# 3-7.net
KiCad netlist of a schematic drawn in Altium Designer
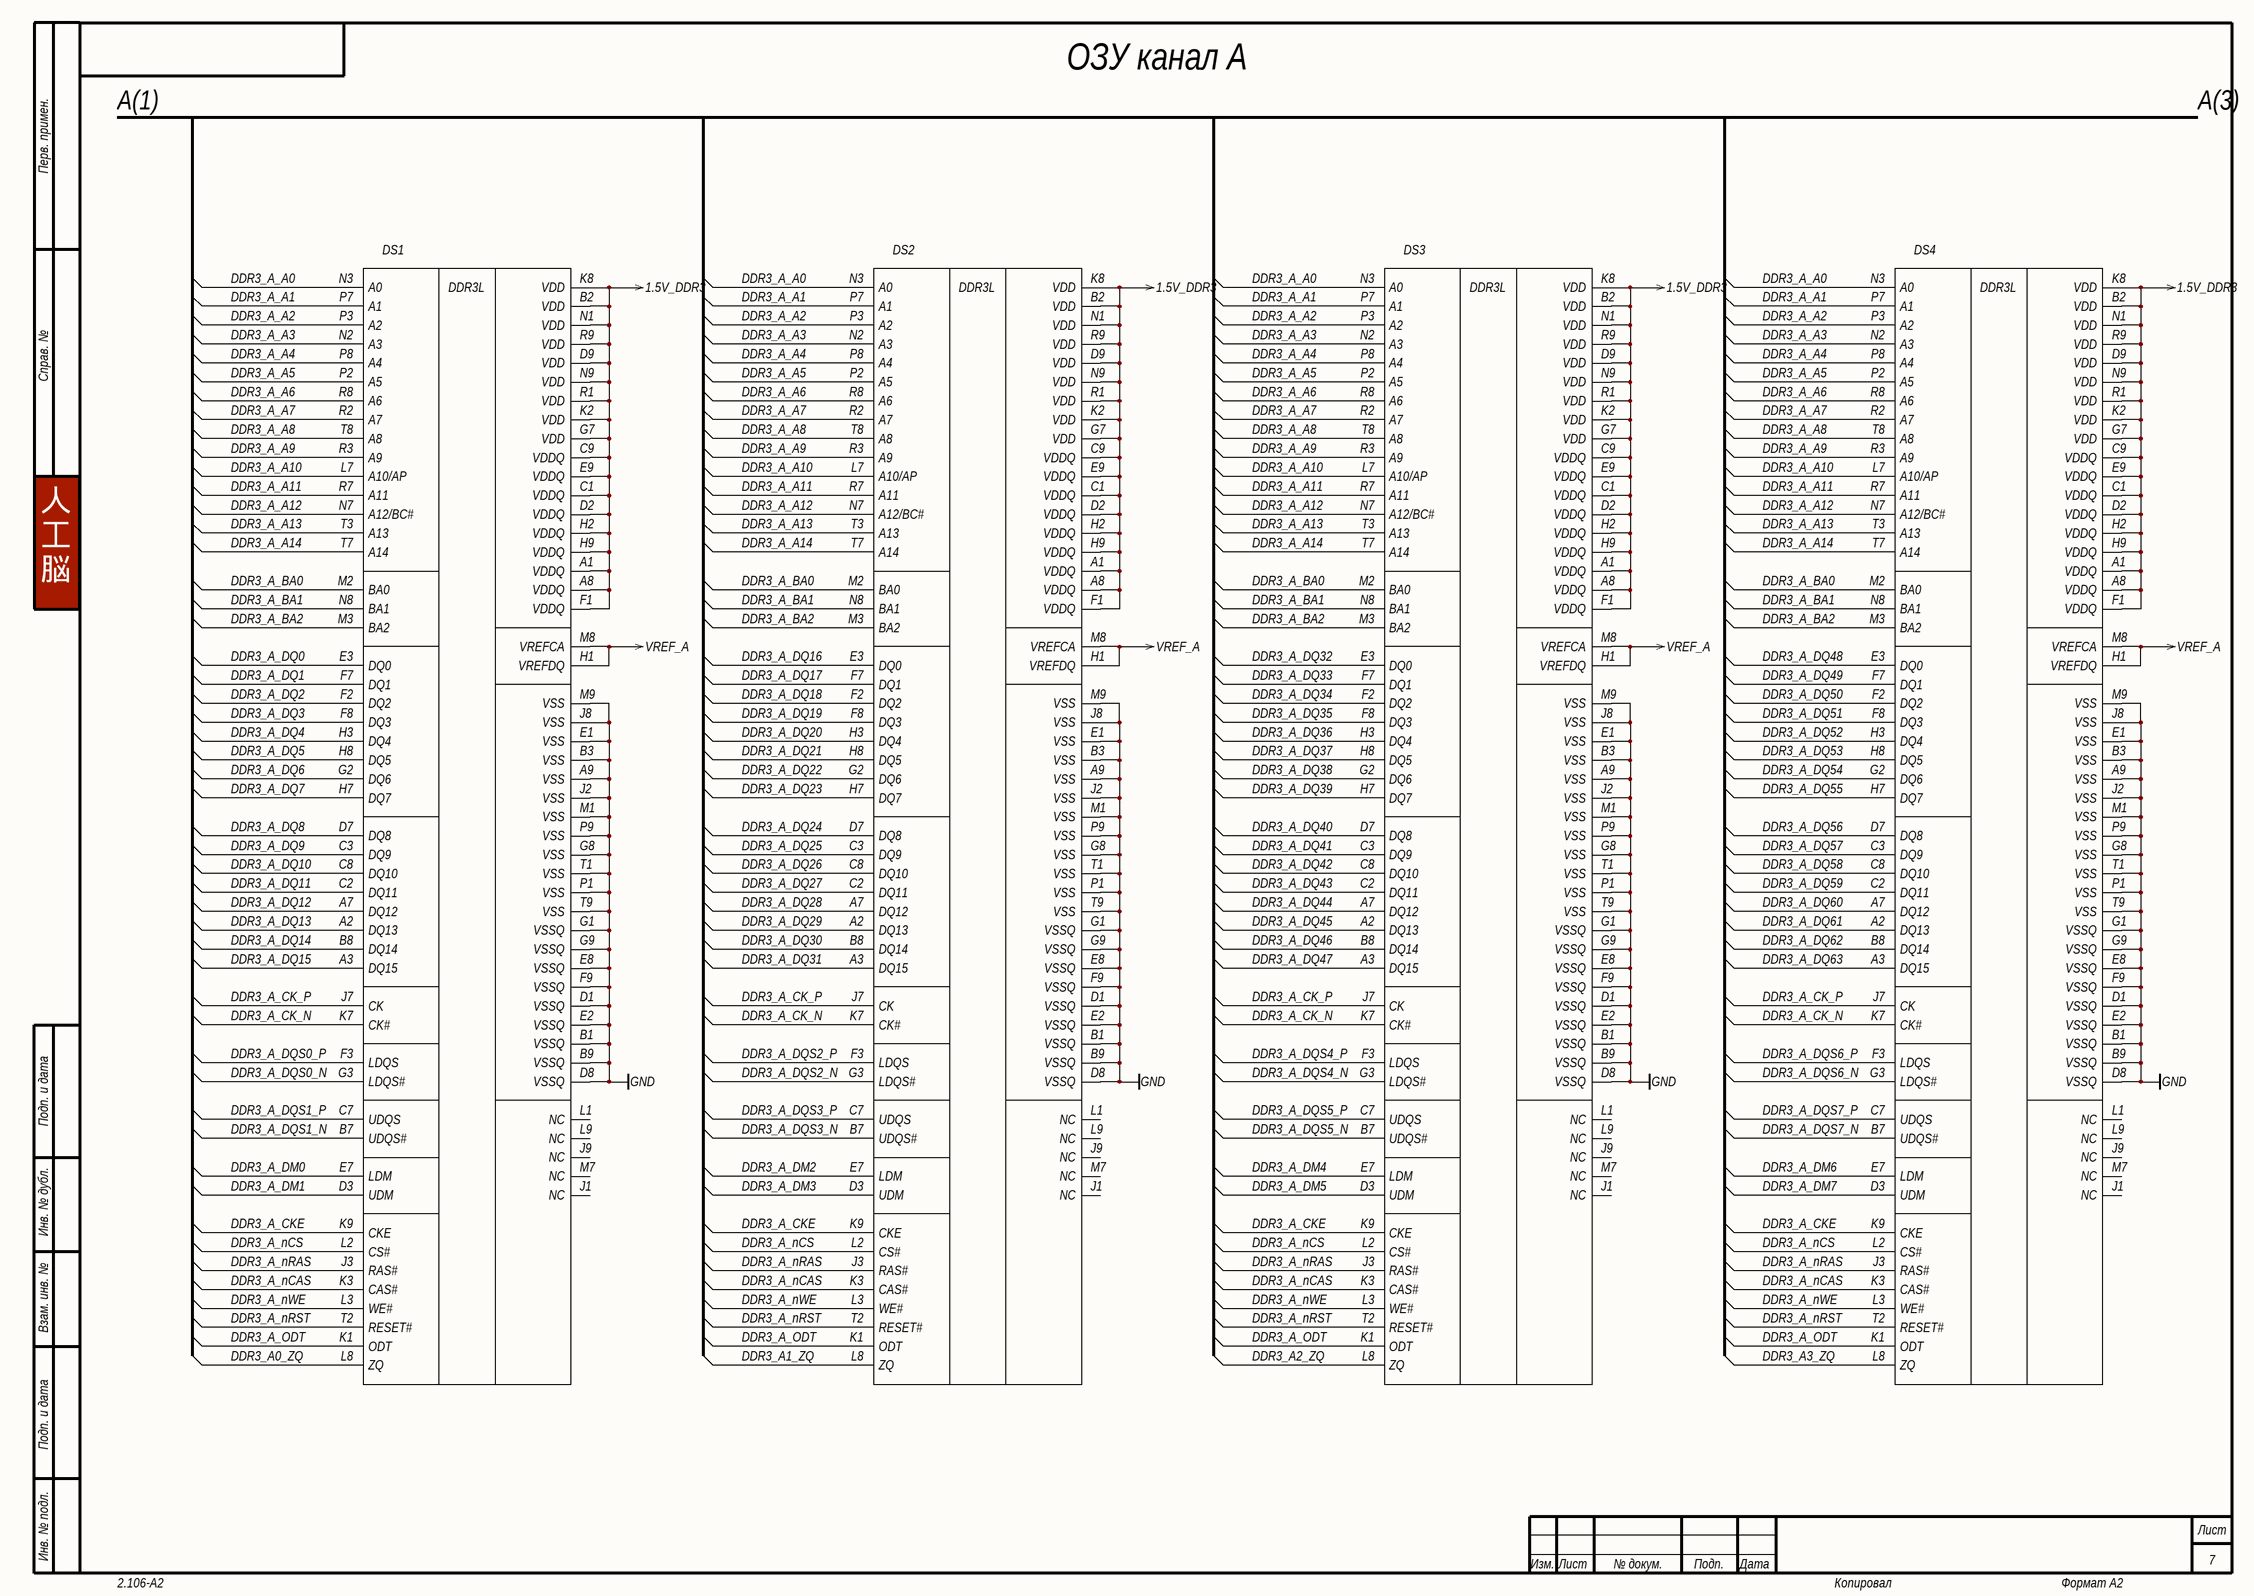
[diagram p0: Э3-7.SchDoc]

(export (version "E")
  (design (tool "Eeschema 10.0.6"))
  (components
    (comp (ref "DS1")
      (value "1")
      (footprint "96-FBGA")
      (description "32 Megx16x8 banks DDR3L SDRAM")
      (fields (field (name "MANUFACTURER") "Micron Technology, Inc."))
      (libsource (lib "Digital") (part "MT41K256M16TW-107IT{colon}P"))
    )
    (comp (ref "DS2")
      (value "1")
      (footprint "96-FBGA")
      (description "32 Megx16x8 banks DDR3L SDRAM")
      (fields (field (name "MANUFACTURER") "Micron Technology, Inc."))
      (libsource (lib "Digital") (part "MT41K256M16TW-107IT{colon}P"))
    )
    (comp (ref "DS3")
      (value "1")
      (footprint "96-FBGA")
      (description "32 Megx16x8 banks DDR3L SDRAM")
      (fields (field (name "MANUFACTURER") "Micron Technology, Inc."))
      (libsource (lib "Digital") (part "MT41K256M16TW-107IT{colon}P"))
    )
    (comp (ref "DS4")
      (value "1")
      (footprint "96-FBGA")
      (description "32 Megx16x8 banks DDR3L SDRAM")
      (fields (field (name "MANUFACTURER") "Micron Technology, Inc."))
      (libsource (lib "Digital") (part "MT41K256M16TW-107IT{colon}P"))
    )
  )
  (nets
    (net (code "1") (name "/DDR3_A0_ZQ") (class "Default")
      (node (ref "DS1") (pin "L8") (pinfunction "ZQ_L8") (pintype "passive"))
    )
    (net (code "2") (name "/DDR3_A1_ZQ") (class "Default")
      (node (ref "DS2") (pin "L8") (pinfunction "ZQ_L8") (pintype "passive"))
    )
    (net (code "3") (name "/DDR3_A2_ZQ") (class "Default")
      (node (ref "DS3") (pin "L8") (pinfunction "ZQ_L8") (pintype "passive"))
    )
    (net (code "4") (name "/DDR3_A3_ZQ") (class "Default")
      (node (ref "DS4") (pin "L8") (pinfunction "ZQ_L8") (pintype "passive"))
    )
    (net (code "5") (name "/DDR3_A_A0") (class "Default")
      (node (ref "DS1") (pin "N3") (pinfunction "A0_N3") (pintype "passive"))
      (node (ref "DS2") (pin "N3") (pinfunction "A0_N3") (pintype "passive"))
      (node (ref "DS3") (pin "N3") (pinfunction "A0_N3") (pintype "passive"))
      (node (ref "DS4") (pin "N3") (pinfunction "A0_N3") (pintype "passive"))
    )
    (net (code "6") (name "/DDR3_A_A1") (class "Default")
      (node (ref "DS1") (pin "P7") (pinfunction "A1_P7") (pintype "passive"))
      (node (ref "DS2") (pin "P7") (pinfunction "A1_P7") (pintype "passive"))
      (node (ref "DS3") (pin "P7") (pinfunction "A1_P7") (pintype "passive"))
      (node (ref "DS4") (pin "P7") (pinfunction "A1_P7") (pintype "passive"))
    )
    (net (code "7") (name "/DDR3_A_A2") (class "Default")
      (node (ref "DS1") (pin "P3") (pinfunction "A2_P3") (pintype "passive"))
      (node (ref "DS2") (pin "P3") (pinfunction "A2_P3") (pintype "passive"))
      (node (ref "DS3") (pin "P3") (pinfunction "A2_P3") (pintype "passive"))
      (node (ref "DS4") (pin "P3") (pinfunction "A2_P3") (pintype "passive"))
    )
    (net (code "8") (name "/DDR3_A_A3") (class "Default")
      (node (ref "DS1") (pin "N2") (pinfunction "A3_N2") (pintype "passive"))
      (node (ref "DS2") (pin "N2") (pinfunction "A3_N2") (pintype "passive"))
      (node (ref "DS3") (pin "N2") (pinfunction "A3_N2") (pintype "passive"))
      (node (ref "DS4") (pin "N2") (pinfunction "A3_N2") (pintype "passive"))
    )
    (net (code "9") (name "/DDR3_A_A4") (class "Default")
      (node (ref "DS1") (pin "P8") (pinfunction "A4_P8") (pintype "passive"))
      (node (ref "DS2") (pin "P8") (pinfunction "A4_P8") (pintype "passive"))
      (node (ref "DS3") (pin "P8") (pinfunction "A4_P8") (pintype "passive"))
      (node (ref "DS4") (pin "P8") (pinfunction "A4_P8") (pintype "passive"))
    )
    (net (code "10") (name "/DDR3_A_A5") (class "Default")
      (node (ref "DS1") (pin "P2") (pinfunction "A5_P2") (pintype "passive"))
      (node (ref "DS2") (pin "P2") (pinfunction "A5_P2") (pintype "passive"))
      (node (ref "DS3") (pin "P2") (pinfunction "A5_P2") (pintype "passive"))
      (node (ref "DS4") (pin "P2") (pinfunction "A5_P2") (pintype "passive"))
    )
    (net (code "11") (name "/DDR3_A_A6") (class "Default")
      (node (ref "DS1") (pin "R8") (pinfunction "A6_R8") (pintype "passive"))
      (node (ref "DS2") (pin "R8") (pinfunction "A6_R8") (pintype "passive"))
      (node (ref "DS3") (pin "R8") (pinfunction "A6_R8") (pintype "passive"))
      (node (ref "DS4") (pin "R8") (pinfunction "A6_R8") (pintype "passive"))
    )
    (net (code "12") (name "/DDR3_A_A7") (class "Default")
      (node (ref "DS1") (pin "R2") (pinfunction "A7_R2") (pintype "passive"))
      (node (ref "DS2") (pin "R2") (pinfunction "A7_R2") (pintype "passive"))
      (node (ref "DS3") (pin "R2") (pinfunction "A7_R2") (pintype "passive"))
      (node (ref "DS4") (pin "R2") (pinfunction "A7_R2") (pintype "passive"))
    )
    (net (code "13") (name "/DDR3_A_A8") (class "Default")
      (node (ref "DS1") (pin "T8") (pinfunction "A8_T8") (pintype "passive"))
      (node (ref "DS2") (pin "T8") (pinfunction "A8_T8") (pintype "passive"))
      (node (ref "DS3") (pin "T8") (pinfunction "A8_T8") (pintype "passive"))
      (node (ref "DS4") (pin "T8") (pinfunction "A8_T8") (pintype "passive"))
    )
    (net (code "14") (name "/DDR3_A_A9") (class "Default")
      (node (ref "DS1") (pin "R3") (pinfunction "A9_R3") (pintype "passive"))
      (node (ref "DS2") (pin "R3") (pinfunction "A9_R3") (pintype "passive"))
      (node (ref "DS3") (pin "R3") (pinfunction "A9_R3") (pintype "passive"))
      (node (ref "DS4") (pin "R3") (pinfunction "A9_R3") (pintype "passive"))
    )
    (net (code "15") (name "/DDR3_A_A10") (class "Default")
      (node (ref "DS1") (pin "L7") (pinfunction "A10/AP_L7") (pintype "passive"))
      (node (ref "DS2") (pin "L7") (pinfunction "A10/AP_L7") (pintype "passive"))
      (node (ref "DS3") (pin "L7") (pinfunction "A10/AP_L7") (pintype "passive"))
      (node (ref "DS4") (pin "L7") (pinfunction "A10/AP_L7") (pintype "passive"))
    )
    (net (code "16") (name "/DDR3_A_A11") (class "Default")
      (node (ref "DS1") (pin "R7") (pinfunction "A11_R7") (pintype "passive"))
      (node (ref "DS2") (pin "R7") (pinfunction "A11_R7") (pintype "passive"))
      (node (ref "DS3") (pin "R7") (pinfunction "A11_R7") (pintype "passive"))
      (node (ref "DS4") (pin "R7") (pinfunction "A11_R7") (pintype "passive"))
    )
    (net (code "17") (name "/DDR3_A_A12") (class "Default")
      (node (ref "DS1") (pin "N7") (pinfunction "A12/BC#_N7") (pintype "passive"))
      (node (ref "DS2") (pin "N7") (pinfunction "A12/BC#_N7") (pintype "passive"))
      (node (ref "DS3") (pin "N7") (pinfunction "A12/BC#_N7") (pintype "passive"))
      (node (ref "DS4") (pin "N7") (pinfunction "A12/BC#_N7") (pintype "passive"))
    )
    (net (code "18") (name "/DDR3_A_A13") (class "Default")
      (node (ref "DS1") (pin "T3") (pinfunction "A13_T3") (pintype "passive"))
      (node (ref "DS2") (pin "T3") (pinfunction "A13_T3") (pintype "passive"))
      (node (ref "DS3") (pin "T3") (pinfunction "A13_T3") (pintype "passive"))
      (node (ref "DS4") (pin "T3") (pinfunction "A13_T3") (pintype "passive"))
    )
    (net (code "19") (name "/DDR3_A_A14") (class "Default")
      (node (ref "DS1") (pin "T7") (pinfunction "A14_T7") (pintype "passive"))
      (node (ref "DS2") (pin "T7") (pinfunction "A14_T7") (pintype "passive"))
      (node (ref "DS3") (pin "T7") (pinfunction "A14_T7") (pintype "passive"))
      (node (ref "DS4") (pin "T7") (pinfunction "A14_T7") (pintype "passive"))
    )
    (net (code "20") (name "/DDR3_A_BA0") (class "Default")
      (node (ref "DS1") (pin "M2") (pinfunction "BA0_M2") (pintype "passive"))
      (node (ref "DS2") (pin "M2") (pinfunction "BA0_M2") (pintype "passive"))
      (node (ref "DS3") (pin "M2") (pinfunction "BA0_M2") (pintype "passive"))
      (node (ref "DS4") (pin "M2") (pinfunction "BA0_M2") (pintype "passive"))
    )
    (net (code "21") (name "/DDR3_A_BA1") (class "Default")
      (node (ref "DS1") (pin "N8") (pinfunction "BA1_N8") (pintype "passive"))
      (node (ref "DS2") (pin "N8") (pinfunction "BA1_N8") (pintype "passive"))
      (node (ref "DS3") (pin "N8") (pinfunction "BA1_N8") (pintype "passive"))
      (node (ref "DS4") (pin "N8") (pinfunction "BA1_N8") (pintype "passive"))
    )
    (net (code "22") (name "/DDR3_A_BA2") (class "Default")
      (node (ref "DS1") (pin "M3") (pinfunction "BA2_M3") (pintype "passive"))
      (node (ref "DS2") (pin "M3") (pinfunction "BA2_M3") (pintype "passive"))
      (node (ref "DS3") (pin "M3") (pinfunction "BA2_M3") (pintype "passive"))
      (node (ref "DS4") (pin "M3") (pinfunction "BA2_M3") (pintype "passive"))
    )
    (net (code "23") (name "/DDR3_A_CKE") (class "Default")
      (node (ref "DS1") (pin "K9") (pinfunction "CKE_K9") (pintype "passive"))
      (node (ref "DS2") (pin "K9") (pinfunction "CKE_K9") (pintype "passive"))
      (node (ref "DS3") (pin "K9") (pinfunction "CKE_K9") (pintype "passive"))
      (node (ref "DS4") (pin "K9") (pinfunction "CKE_K9") (pintype "passive"))
    )
    (net (code "24") (name "/DDR3_A_CK_N") (class "Default")
      (node (ref "DS1") (pin "K7") (pinfunction "CK#_K7") (pintype "passive"))
      (node (ref "DS2") (pin "K7") (pinfunction "CK#_K7") (pintype "passive"))
      (node (ref "DS3") (pin "K7") (pinfunction "CK#_K7") (pintype "passive"))
      (node (ref "DS4") (pin "K7") (pinfunction "CK#_K7") (pintype "passive"))
    )
    (net (code "25") (name "/DDR3_A_CK_P") (class "Default")
      (node (ref "DS1") (pin "J7") (pinfunction "CK_J7") (pintype "passive"))
      (node (ref "DS2") (pin "J7") (pinfunction "CK_J7") (pintype "passive"))
      (node (ref "DS3") (pin "J7") (pinfunction "CK_J7") (pintype "passive"))
      (node (ref "DS4") (pin "J7") (pinfunction "CK_J7") (pintype "passive"))
    )
    (net (code "26") (name "/DDR3_A_DM0") (class "Default")
      (node (ref "DS1") (pin "E7") (pinfunction "LDM_E7") (pintype "passive"))
    )
    (net (code "27") (name "/DDR3_A_DM1") (class "Default")
      (node (ref "DS1") (pin "D3") (pinfunction "UDM_D3") (pintype "passive"))
    )
    (net (code "28") (name "/DDR3_A_DM2") (class "Default")
      (node (ref "DS2") (pin "E7") (pinfunction "LDM_E7") (pintype "passive"))
    )
    (net (code "29") (name "/DDR3_A_DM3") (class "Default")
      (node (ref "DS2") (pin "D3") (pinfunction "UDM_D3") (pintype "passive"))
    )
    (net (code "30") (name "/DDR3_A_DM4") (class "Default")
      (node (ref "DS3") (pin "E7") (pinfunction "LDM_E7") (pintype "passive"))
    )
    (net (code "31") (name "/DDR3_A_DM5") (class "Default")
      (node (ref "DS3") (pin "D3") (pinfunction "UDM_D3") (pintype "passive"))
    )
    (net (code "32") (name "/DDR3_A_DM6") (class "Default")
      (node (ref "DS4") (pin "E7") (pinfunction "LDM_E7") (pintype "passive"))
    )
    (net (code "33") (name "/DDR3_A_DM7") (class "Default")
      (node (ref "DS4") (pin "D3") (pinfunction "UDM_D3") (pintype "passive"))
    )
    (net (code "34") (name "/DDR3_A_DQ0") (class "Default")
      (node (ref "DS1") (pin "E3") (pinfunction "DQ0_E3") (pintype "passive"))
    )
    (net (code "35") (name "/DDR3_A_DQ1") (class "Default")
      (node (ref "DS1") (pin "F7") (pinfunction "DQ1_F7") (pintype "passive"))
    )
    (net (code "36") (name "/DDR3_A_DQ2") (class "Default")
      (node (ref "DS1") (pin "F2") (pinfunction "DQ2_F2") (pintype "passive"))
    )
    (net (code "37") (name "/DDR3_A_DQ3") (class "Default")
      (node (ref "DS1") (pin "F8") (pinfunction "DQ3_F8") (pintype "passive"))
    )
    (net (code "38") (name "/DDR3_A_DQ4") (class "Default")
      (node (ref "DS1") (pin "H3") (pinfunction "DQ4_H3") (pintype "passive"))
    )
    (net (code "39") (name "/DDR3_A_DQ5") (class "Default")
      (node (ref "DS1") (pin "H8") (pinfunction "DQ5_H8") (pintype "passive"))
    )
    (net (code "40") (name "/DDR3_A_DQ6") (class "Default")
      (node (ref "DS1") (pin "G2") (pinfunction "DQ6_G2") (pintype "passive"))
    )
    (net (code "41") (name "/DDR3_A_DQ7") (class "Default")
      (node (ref "DS1") (pin "H7") (pinfunction "DQ7_H7") (pintype "passive"))
    )
    (net (code "42") (name "/DDR3_A_DQ8") (class "Default")
      (node (ref "DS1") (pin "D7") (pinfunction "DQ8_D7") (pintype "passive"))
    )
    (net (code "43") (name "/DDR3_A_DQ9") (class "Default")
      (node (ref "DS1") (pin "C3") (pinfunction "DQ9_C3") (pintype "passive"))
    )
    (net (code "44") (name "/DDR3_A_DQ10") (class "Default")
      (node (ref "DS1") (pin "C8") (pinfunction "DQ10_C8") (pintype "passive"))
    )
    (net (code "45") (name "/DDR3_A_DQ11") (class "Default")
      (node (ref "DS1") (pin "C2") (pinfunction "DQ11_C2") (pintype "passive"))
    )
    (net (code "46") (name "/DDR3_A_DQ12") (class "Default")
      (node (ref "DS1") (pin "A7") (pinfunction "DQ12_A7") (pintype "passive"))
    )
    (net (code "47") (name "/DDR3_A_DQ13") (class "Default")
      (node (ref "DS1") (pin "A2") (pinfunction "DQ13_A2") (pintype "passive"))
    )
    (net (code "48") (name "/DDR3_A_DQ14") (class "Default")
      (node (ref "DS1") (pin "B8") (pinfunction "DQ14_B8") (pintype "passive"))
    )
    (net (code "49") (name "/DDR3_A_DQ15") (class "Default")
      (node (ref "DS1") (pin "A3") (pinfunction "DQ15_A3") (pintype "passive"))
    )
    (net (code "50") (name "/DDR3_A_DQ16") (class "Default")
      (node (ref "DS2") (pin "E3") (pinfunction "DQ0_E3") (pintype "passive"))
    )
    (net (code "51") (name "/DDR3_A_DQ17") (class "Default")
      (node (ref "DS2") (pin "F7") (pinfunction "DQ1_F7") (pintype "passive"))
    )
    (net (code "52") (name "/DDR3_A_DQ18") (class "Default")
      (node (ref "DS2") (pin "F2") (pinfunction "DQ2_F2") (pintype "passive"))
    )
    (net (code "53") (name "/DDR3_A_DQ19") (class "Default")
      (node (ref "DS2") (pin "F8") (pinfunction "DQ3_F8") (pintype "passive"))
    )
    (net (code "54") (name "/DDR3_A_DQ20") (class "Default")
      (node (ref "DS2") (pin "H3") (pinfunction "DQ4_H3") (pintype "passive"))
    )
    (net (code "55") (name "/DDR3_A_DQ21") (class "Default")
      (node (ref "DS2") (pin "H8") (pinfunction "DQ5_H8") (pintype "passive"))
    )
    (net (code "56") (name "/DDR3_A_DQ22") (class "Default")
      (node (ref "DS2") (pin "G2") (pinfunction "DQ6_G2") (pintype "passive"))
    )
    (net (code "57") (name "/DDR3_A_DQ23") (class "Default")
      (node (ref "DS2") (pin "H7") (pinfunction "DQ7_H7") (pintype "passive"))
    )
    (net (code "58") (name "/DDR3_A_DQ24") (class "Default")
      (node (ref "DS2") (pin "D7") (pinfunction "DQ8_D7") (pintype "passive"))
    )
    (net (code "59") (name "/DDR3_A_DQ25") (class "Default")
      (node (ref "DS2") (pin "C3") (pinfunction "DQ9_C3") (pintype "passive"))
    )
    (net (code "60") (name "/DDR3_A_DQ26") (class "Default")
      (node (ref "DS2") (pin "C8") (pinfunction "DQ10_C8") (pintype "passive"))
    )
    (net (code "61") (name "/DDR3_A_DQ27") (class "Default")
      (node (ref "DS2") (pin "C2") (pinfunction "DQ11_C2") (pintype "passive"))
    )
    (net (code "62") (name "/DDR3_A_DQ28") (class "Default")
      (node (ref "DS2") (pin "A7") (pinfunction "DQ12_A7") (pintype "passive"))
    )
    (net (code "63") (name "/DDR3_A_DQ29") (class "Default")
      (node (ref "DS2") (pin "A2") (pinfunction "DQ13_A2") (pintype "passive"))
    )
    (net (code "64") (name "/DDR3_A_DQ30") (class "Default")
      (node (ref "DS2") (pin "B8") (pinfunction "DQ14_B8") (pintype "passive"))
    )
    (net (code "65") (name "/DDR3_A_DQ31") (class "Default")
      (node (ref "DS2") (pin "A3") (pinfunction "DQ15_A3") (pintype "passive"))
    )
    (net (code "66") (name "/DDR3_A_DQ32") (class "Default")
      (node (ref "DS3") (pin "E3") (pinfunction "DQ0_E3") (pintype "passive"))
    )
    (net (code "67") (name "/DDR3_A_DQ33") (class "Default")
      (node (ref "DS3") (pin "F7") (pinfunction "DQ1_F7") (pintype "passive"))
    )
    (net (code "68") (name "/DDR3_A_DQ34") (class "Default")
      (node (ref "DS3") (pin "F2") (pinfunction "DQ2_F2") (pintype "passive"))
    )
    (net (code "69") (name "/DDR3_A_DQ35") (class "Default")
      (node (ref "DS3") (pin "F8") (pinfunction "DQ3_F8") (pintype "passive"))
    )
    (net (code "70") (name "/DDR3_A_DQ36") (class "Default")
      (node (ref "DS3") (pin "H3") (pinfunction "DQ4_H3") (pintype "passive"))
    )
    (net (code "71") (name "/DDR3_A_DQ37") (class "Default")
      (node (ref "DS3") (pin "H8") (pinfunction "DQ5_H8") (pintype "passive"))
    )
    (net (code "72") (name "/DDR3_A_DQ38") (class "Default")
      (node (ref "DS3") (pin "G2") (pinfunction "DQ6_G2") (pintype "passive"))
    )
    (net (code "73") (name "/DDR3_A_DQ39") (class "Default")
      (node (ref "DS3") (pin "H7") (pinfunction "DQ7_H7") (pintype "passive"))
    )
    (net (code "74") (name "/DDR3_A_DQ40") (class "Default")
      (node (ref "DS3") (pin "D7") (pinfunction "DQ8_D7") (pintype "passive"))
    )
    (net (code "75") (name "/DDR3_A_DQ41") (class "Default")
      (node (ref "DS3") (pin "C3") (pinfunction "DQ9_C3") (pintype "passive"))
    )
    (net (code "76") (name "/DDR3_A_DQ42") (class "Default")
      (node (ref "DS3") (pin "C8") (pinfunction "DQ10_C8") (pintype "passive"))
    )
    (net (code "77") (name "/DDR3_A_DQ43") (class "Default")
      (node (ref "DS3") (pin "C2") (pinfunction "DQ11_C2") (pintype "passive"))
    )
    (net (code "78") (name "/DDR3_A_DQ44") (class "Default")
      (node (ref "DS3") (pin "A7") (pinfunction "DQ12_A7") (pintype "passive"))
    )
    (net (code "79") (name "/DDR3_A_DQ45") (class "Default")
      (node (ref "DS3") (pin "A2") (pinfunction "DQ13_A2") (pintype "passive"))
    )
    (net (code "80") (name "/DDR3_A_DQ46") (class "Default")
      (node (ref "DS3") (pin "B8") (pinfunction "DQ14_B8") (pintype "passive"))
    )
    (net (code "81") (name "/DDR3_A_DQ47") (class "Default")
      (node (ref "DS3") (pin "A3") (pinfunction "DQ15_A3") (pintype "passive"))
    )
    (net (code "82") (name "/DDR3_A_DQ48") (class "Default")
      (node (ref "DS4") (pin "E3") (pinfunction "DQ0_E3") (pintype "passive"))
    )
    (net (code "83") (name "/DDR3_A_DQ49") (class "Default")
      (node (ref "DS4") (pin "F7") (pinfunction "DQ1_F7") (pintype "passive"))
    )
    (net (code "84") (name "/DDR3_A_DQ50") (class "Default")
      (node (ref "DS4") (pin "F2") (pinfunction "DQ2_F2") (pintype "passive"))
    )
    (net (code "85") (name "/DDR3_A_DQ51") (class "Default")
      (node (ref "DS4") (pin "F8") (pinfunction "DQ3_F8") (pintype "passive"))
    )
    (net (code "86") (name "/DDR3_A_DQ52") (class "Default")
      (node (ref "DS4") (pin "H3") (pinfunction "DQ4_H3") (pintype "passive"))
    )
    (net (code "87") (name "/DDR3_A_DQ53") (class "Default")
      (node (ref "DS4") (pin "H8") (pinfunction "DQ5_H8") (pintype "passive"))
    )
    (net (code "88") (name "/DDR3_A_DQ54") (class "Default")
      (node (ref "DS4") (pin "G2") (pinfunction "DQ6_G2") (pintype "passive"))
    )
    (net (code "89") (name "/DDR3_A_DQ55") (class "Default")
      (node (ref "DS4") (pin "H7") (pinfunction "DQ7_H7") (pintype "passive"))
    )
    (net (code "90") (name "/DDR3_A_DQ56") (class "Default")
      (node (ref "DS4") (pin "D7") (pinfunction "DQ8_D7") (pintype "passive"))
    )
    (net (code "91") (name "/DDR3_A_DQ57") (class "Default")
      (node (ref "DS4") (pin "C3") (pinfunction "DQ9_C3") (pintype "passive"))
    )
    (net (code "92") (name "/DDR3_A_DQ58") (class "Default")
      (node (ref "DS4") (pin "C8") (pinfunction "DQ10_C8") (pintype "passive"))
    )
    (net (code "93") (name "/DDR3_A_DQ59") (class "Default")
      (node (ref "DS4") (pin "C2") (pinfunction "DQ11_C2") (pintype "passive"))
    )
    (net (code "94") (name "/DDR3_A_DQ60") (class "Default")
      (node (ref "DS4") (pin "A7") (pinfunction "DQ12_A7") (pintype "passive"))
    )
    (net (code "95") (name "/DDR3_A_DQ61") (class "Default")
      (node (ref "DS4") (pin "A2") (pinfunction "DQ13_A2") (pintype "passive"))
    )
    (net (code "96") (name "/DDR3_A_DQ62") (class "Default")
      (node (ref "DS4") (pin "B8") (pinfunction "DQ14_B8") (pintype "passive"))
    )
    (net (code "97") (name "/DDR3_A_DQ63") (class "Default")
      (node (ref "DS4") (pin "A3") (pinfunction "DQ15_A3") (pintype "passive"))
    )
    (net (code "98") (name "/DDR3_A_DQS0_N") (class "Default")
      (node (ref "DS1") (pin "G3") (pinfunction "LDQS#_G3") (pintype "passive"))
    )
    (net (code "99") (name "/DDR3_A_DQS0_P") (class "Default")
      (node (ref "DS1") (pin "F3") (pinfunction "LDQS_F3") (pintype "passive"))
    )
    (net (code "100") (name "/DDR3_A_DQS1_N") (class "Default")
      (node (ref "DS1") (pin "B7") (pinfunction "UDQS#_B7") (pintype "passive"))
    )
    (net (code "101") (name "/DDR3_A_DQS1_P") (class "Default")
      (node (ref "DS1") (pin "C7") (pinfunction "UDQS_C7") (pintype "passive"))
    )
    (net (code "102") (name "/DDR3_A_DQS2_N") (class "Default")
      (node (ref "DS2") (pin "G3") (pinfunction "LDQS#_G3") (pintype "passive"))
    )
    (net (code "103") (name "/DDR3_A_DQS2_P") (class "Default")
      (node (ref "DS2") (pin "F3") (pinfunction "LDQS_F3") (pintype "passive"))
    )
    (net (code "104") (name "/DDR3_A_DQS3_N") (class "Default")
      (node (ref "DS2") (pin "B7") (pinfunction "UDQS#_B7") (pintype "passive"))
    )
    (net (code "105") (name "/DDR3_A_DQS3_P") (class "Default")
      (node (ref "DS2") (pin "C7") (pinfunction "UDQS_C7") (pintype "passive"))
    )
    (net (code "106") (name "/DDR3_A_DQS4_N") (class "Default")
      (node (ref "DS3") (pin "G3") (pinfunction "LDQS#_G3") (pintype "passive"))
    )
    (net (code "107") (name "/DDR3_A_DQS4_P") (class "Default")
      (node (ref "DS3") (pin "F3") (pinfunction "LDQS_F3") (pintype "passive"))
    )
    (net (code "108") (name "/DDR3_A_DQS5_N") (class "Default")
      (node (ref "DS3") (pin "B7") (pinfunction "UDQS#_B7") (pintype "passive"))
    )
    (net (code "109") (name "/DDR3_A_DQS5_P") (class "Default")
      (node (ref "DS3") (pin "C7") (pinfunction "UDQS_C7") (pintype "passive"))
    )
    (net (code "110") (name "/DDR3_A_DQS6_N") (class "Default")
      (node (ref "DS4") (pin "G3") (pinfunction "LDQS#_G3") (pintype "passive"))
    )
    (net (code "111") (name "/DDR3_A_DQS6_P") (class "Default")
      (node (ref "DS4") (pin "F3") (pinfunction "LDQS_F3") (pintype "passive"))
    )
    (net (code "112") (name "/DDR3_A_DQS7_N") (class "Default")
      (node (ref "DS4") (pin "B7") (pinfunction "UDQS#_B7") (pintype "passive"))
    )
    (net (code "113") (name "/DDR3_A_DQS7_P") (class "Default")
      (node (ref "DS4") (pin "C7") (pinfunction "UDQS_C7") (pintype "passive"))
    )
    (net (code "114") (name "/DDR3_A_ODT") (class "Default")
      (node (ref "DS1") (pin "K1") (pinfunction "ODT_K1") (pintype "passive"))
      (node (ref "DS2") (pin "K1") (pinfunction "ODT_K1") (pintype "passive"))
      (node (ref "DS3") (pin "K1") (pinfunction "ODT_K1") (pintype "passive"))
      (node (ref "DS4") (pin "K1") (pinfunction "ODT_K1") (pintype "passive"))
    )
    (net (code "115") (name "/DDR3_A_nCAS") (class "Default")
      (node (ref "DS1") (pin "K3") (pinfunction "CAS#_K3") (pintype "passive"))
      (node (ref "DS2") (pin "K3") (pinfunction "CAS#_K3") (pintype "passive"))
      (node (ref "DS3") (pin "K3") (pinfunction "CAS#_K3") (pintype "passive"))
      (node (ref "DS4") (pin "K3") (pinfunction "CAS#_K3") (pintype "passive"))
    )
    (net (code "116") (name "/DDR3_A_nCS") (class "Default")
      (node (ref "DS1") (pin "L2") (pinfunction "CS#_L2") (pintype "passive"))
      (node (ref "DS2") (pin "L2") (pinfunction "CS#_L2") (pintype "passive"))
      (node (ref "DS3") (pin "L2") (pinfunction "CS#_L2") (pintype "passive"))
      (node (ref "DS4") (pin "L2") (pinfunction "CS#_L2") (pintype "passive"))
    )
    (net (code "117") (name "/DDR3_A_nRAS") (class "Default")
      (node (ref "DS1") (pin "J3") (pinfunction "RAS#_J3") (pintype "passive"))
      (node (ref "DS2") (pin "J3") (pinfunction "RAS#_J3") (pintype "passive"))
      (node (ref "DS3") (pin "J3") (pinfunction "RAS#_J3") (pintype "passive"))
      (node (ref "DS4") (pin "J3") (pinfunction "RAS#_J3") (pintype "passive"))
    )
    (net (code "118") (name "/DDR3_A_nRST") (class "Default")
      (node (ref "DS1") (pin "T2") (pinfunction "RESET#_T2") (pintype "passive"))
      (node (ref "DS2") (pin "T2") (pinfunction "RESET#_T2") (pintype "passive"))
      (node (ref "DS3") (pin "T2") (pinfunction "RESET#_T2") (pintype "passive"))
      (node (ref "DS4") (pin "T2") (pinfunction "RESET#_T2") (pintype "passive"))
    )
    (net (code "119") (name "/DDR3_A_nWE") (class "Default")
      (node (ref "DS1") (pin "L3") (pinfunction "WE#_L3") (pintype "passive"))
      (node (ref "DS2") (pin "L3") (pinfunction "WE#_L3") (pintype "passive"))
      (node (ref "DS3") (pin "L3") (pinfunction "WE#_L3") (pintype "passive"))
      (node (ref "DS4") (pin "L3") (pinfunction "WE#_L3") (pintype "passive"))
    )
    (net (code "120") (name "1.5V_DDR3") (class "Default")
      (node (ref "DS1") (pin "A1") (pinfunction "VDDQ_A1") (pintype "passive"))
      (node (ref "DS1") (pin "A8") (pinfunction "VDDQ_A8") (pintype "passive"))
      (node (ref "DS1") (pin "B2") (pinfunction "VDD_B2") (pintype "passive"))
      (node (ref "DS1") (pin "C1") (pinfunction "VDDQ_C1") (pintype "passive"))
      (node (ref "DS1") (pin "C9") (pinfunction "VDDQ_C9") (pintype "passive"))
      (node (ref "DS1") (pin "D2") (pinfunction "VDDQ_D2") (pintype "passive"))
      (node (ref "DS1") (pin "D9") (pinfunction "VDD_D9") (pintype "passive"))
      (node (ref "DS1") (pin "E9") (pinfunction "VDDQ_E9") (pintype "passive"))
      (node (ref "DS1") (pin "F1") (pinfunction "VDDQ_F1") (pintype "passive"))
      (node (ref "DS1") (pin "G7") (pinfunction "VDD_G7") (pintype "passive"))
      (node (ref "DS1") (pin "H2") (pinfunction "VDDQ_H2") (pintype "passive"))
      (node (ref "DS1") (pin "H9") (pinfunction "VDDQ_H9") (pintype "passive"))
      (node (ref "DS1") (pin "K2") (pinfunction "VDD_K2") (pintype "passive"))
      (node (ref "DS1") (pin "K8") (pinfunction "VDD_K8") (pintype "passive"))
      (node (ref "DS1") (pin "N1") (pinfunction "VDD_N1") (pintype "passive"))
      (node (ref "DS1") (pin "N9") (pinfunction "VDD_N9") (pintype "passive"))
      (node (ref "DS1") (pin "R1") (pinfunction "VDD_R1") (pintype "passive"))
      (node (ref "DS1") (pin "R9") (pinfunction "VDD_R9") (pintype "passive"))
      (node (ref "DS2") (pin "A1") (pinfunction "VDDQ_A1") (pintype "passive"))
      (node (ref "DS2") (pin "A8") (pinfunction "VDDQ_A8") (pintype "passive"))
      (node (ref "DS2") (pin "B2") (pinfunction "VDD_B2") (pintype "passive"))
      (node (ref "DS2") (pin "C1") (pinfunction "VDDQ_C1") (pintype "passive"))
      (node (ref "DS2") (pin "C9") (pinfunction "VDDQ_C9") (pintype "passive"))
      (node (ref "DS2") (pin "D2") (pinfunction "VDDQ_D2") (pintype "passive"))
      (node (ref "DS2") (pin "D9") (pinfunction "VDD_D9") (pintype "passive"))
      (node (ref "DS2") (pin "E9") (pinfunction "VDDQ_E9") (pintype "passive"))
      (node (ref "DS2") (pin "F1") (pinfunction "VDDQ_F1") (pintype "passive"))
      (node (ref "DS2") (pin "G7") (pinfunction "VDD_G7") (pintype "passive"))
      (node (ref "DS2") (pin "H2") (pinfunction "VDDQ_H2") (pintype "passive"))
      (node (ref "DS2") (pin "H9") (pinfunction "VDDQ_H9") (pintype "passive"))
      (node (ref "DS2") (pin "K2") (pinfunction "VDD_K2") (pintype "passive"))
      (node (ref "DS2") (pin "K8") (pinfunction "VDD_K8") (pintype "passive"))
      (node (ref "DS2") (pin "N1") (pinfunction "VDD_N1") (pintype "passive"))
      (node (ref "DS2") (pin "N9") (pinfunction "VDD_N9") (pintype "passive"))
      (node (ref "DS2") (pin "R1") (pinfunction "VDD_R1") (pintype "passive"))
      (node (ref "DS2") (pin "R9") (pinfunction "VDD_R9") (pintype "passive"))
      (node (ref "DS3") (pin "A1") (pinfunction "VDDQ_A1") (pintype "passive"))
      (node (ref "DS3") (pin "A8") (pinfunction "VDDQ_A8") (pintype "passive"))
      (node (ref "DS3") (pin "B2") (pinfunction "VDD_B2") (pintype "passive"))
      (node (ref "DS3") (pin "C1") (pinfunction "VDDQ_C1") (pintype "passive"))
      (node (ref "DS3") (pin "C9") (pinfunction "VDDQ_C9") (pintype "passive"))
      (node (ref "DS3") (pin "D2") (pinfunction "VDDQ_D2") (pintype "passive"))
      (node (ref "DS3") (pin "D9") (pinfunction "VDD_D9") (pintype "passive"))
      (node (ref "DS3") (pin "E9") (pinfunction "VDDQ_E9") (pintype "passive"))
      (node (ref "DS3") (pin "F1") (pinfunction "VDDQ_F1") (pintype "passive"))
      (node (ref "DS3") (pin "G7") (pinfunction "VDD_G7") (pintype "passive"))
      (node (ref "DS3") (pin "H2") (pinfunction "VDDQ_H2") (pintype "passive"))
      (node (ref "DS3") (pin "H9") (pinfunction "VDDQ_H9") (pintype "passive"))
      (node (ref "DS3") (pin "K2") (pinfunction "VDD_K2") (pintype "passive"))
      (node (ref "DS3") (pin "K8") (pinfunction "VDD_K8") (pintype "passive"))
      (node (ref "DS3") (pin "N1") (pinfunction "VDD_N1") (pintype "passive"))
      (node (ref "DS3") (pin "N9") (pinfunction "VDD_N9") (pintype "passive"))
      (node (ref "DS3") (pin "R1") (pinfunction "VDD_R1") (pintype "passive"))
      (node (ref "DS3") (pin "R9") (pinfunction "VDD_R9") (pintype "passive"))
      (node (ref "DS4") (pin "A1") (pinfunction "VDDQ_A1") (pintype "passive"))
      (node (ref "DS4") (pin "A8") (pinfunction "VDDQ_A8") (pintype "passive"))
      (node (ref "DS4") (pin "B2") (pinfunction "VDD_B2") (pintype "passive"))
      (node (ref "DS4") (pin "C1") (pinfunction "VDDQ_C1") (pintype "passive"))
      (node (ref "DS4") (pin "C9") (pinfunction "VDDQ_C9") (pintype "passive"))
      (node (ref "DS4") (pin "D2") (pinfunction "VDDQ_D2") (pintype "passive"))
      (node (ref "DS4") (pin "D9") (pinfunction "VDD_D9") (pintype "passive"))
      (node (ref "DS4") (pin "E9") (pinfunction "VDDQ_E9") (pintype "passive"))
      (node (ref "DS4") (pin "F1") (pinfunction "VDDQ_F1") (pintype "passive"))
      (node (ref "DS4") (pin "G7") (pinfunction "VDD_G7") (pintype "passive"))
      (node (ref "DS4") (pin "H2") (pinfunction "VDDQ_H2") (pintype "passive"))
      (node (ref "DS4") (pin "H9") (pinfunction "VDDQ_H9") (pintype "passive"))
      (node (ref "DS4") (pin "K2") (pinfunction "VDD_K2") (pintype "passive"))
      (node (ref "DS4") (pin "K8") (pinfunction "VDD_K8") (pintype "passive"))
      (node (ref "DS4") (pin "N1") (pinfunction "VDD_N1") (pintype "passive"))
      (node (ref "DS4") (pin "N9") (pinfunction "VDD_N9") (pintype "passive"))
      (node (ref "DS4") (pin "R1") (pinfunction "VDD_R1") (pintype "passive"))
      (node (ref "DS4") (pin "R9") (pinfunction "VDD_R9") (pintype "passive"))
    )
    (net (code "121") (name "GND") (class "Default")
      (node (ref "DS1") (pin "A9") (pinfunction "VSS_A9") (pintype "passive"))
      (node (ref "DS1") (pin "B1") (pinfunction "VSSQ_B1") (pintype "passive"))
      (node (ref "DS1") (pin "B3") (pinfunction "VSS_B3") (pintype "passive"))
      (node (ref "DS1") (pin "B9") (pinfunction "VSSQ_B9") (pintype "passive"))
      (node (ref "DS1") (pin "D1") (pinfunction "VSSQ_D1") (pintype "passive"))
      (node (ref "DS1") (pin "D8") (pinfunction "VSSQ_D8") (pintype "passive"))
      (node (ref "DS1") (pin "E1") (pinfunction "VSS_E1") (pintype "passive"))
      (node (ref "DS1") (pin "E2") (pinfunction "VSSQ_E2") (pintype "passive"))
      (node (ref "DS1") (pin "E8") (pinfunction "VSSQ_E8") (pintype "passive"))
      (node (ref "DS1") (pin "F9") (pinfunction "VSSQ_F9") (pintype "passive"))
      (node (ref "DS1") (pin "G1") (pinfunction "VSSQ_G1") (pintype "passive"))
      (node (ref "DS1") (pin "G8") (pinfunction "VSS_G8") (pintype "passive"))
      (node (ref "DS1") (pin "G9") (pinfunction "VSSQ_G9") (pintype "passive"))
      (node (ref "DS1") (pin "J2") (pinfunction "VSS_J2") (pintype "passive"))
      (node (ref "DS1") (pin "J8") (pinfunction "VSS_J8") (pintype "passive"))
      (node (ref "DS1") (pin "M1") (pinfunction "VSS_M1") (pintype "passive"))
      (node (ref "DS1") (pin "M9") (pinfunction "VSS_M9") (pintype "passive"))
      (node (ref "DS1") (pin "P1") (pinfunction "VSS_P1") (pintype "passive"))
      (node (ref "DS1") (pin "P9") (pinfunction "VSS_P9") (pintype "passive"))
      (node (ref "DS1") (pin "T1") (pinfunction "VSS_T1") (pintype "passive"))
      (node (ref "DS1") (pin "T9") (pinfunction "VSS_T9") (pintype "passive"))
      (node (ref "DS2") (pin "A9") (pinfunction "VSS_A9") (pintype "passive"))
      (node (ref "DS2") (pin "B1") (pinfunction "VSSQ_B1") (pintype "passive"))
      (node (ref "DS2") (pin "B3") (pinfunction "VSS_B3") (pintype "passive"))
      (node (ref "DS2") (pin "B9") (pinfunction "VSSQ_B9") (pintype "passive"))
      (node (ref "DS2") (pin "D1") (pinfunction "VSSQ_D1") (pintype "passive"))
      (node (ref "DS2") (pin "D8") (pinfunction "VSSQ_D8") (pintype "passive"))
      (node (ref "DS2") (pin "E1") (pinfunction "VSS_E1") (pintype "passive"))
      (node (ref "DS2") (pin "E2") (pinfunction "VSSQ_E2") (pintype "passive"))
      (node (ref "DS2") (pin "E8") (pinfunction "VSSQ_E8") (pintype "passive"))
      (node (ref "DS2") (pin "F9") (pinfunction "VSSQ_F9") (pintype "passive"))
      (node (ref "DS2") (pin "G1") (pinfunction "VSSQ_G1") (pintype "passive"))
      (node (ref "DS2") (pin "G8") (pinfunction "VSS_G8") (pintype "passive"))
      (node (ref "DS2") (pin "G9") (pinfunction "VSSQ_G9") (pintype "passive"))
      (node (ref "DS2") (pin "J2") (pinfunction "VSS_J2") (pintype "passive"))
      (node (ref "DS2") (pin "J8") (pinfunction "VSS_J8") (pintype "passive"))
      (node (ref "DS2") (pin "M1") (pinfunction "VSS_M1") (pintype "passive"))
      (node (ref "DS2") (pin "M9") (pinfunction "VSS_M9") (pintype "passive"))
      (node (ref "DS2") (pin "P1") (pinfunction "VSS_P1") (pintype "passive"))
      (node (ref "DS2") (pin "P9") (pinfunction "VSS_P9") (pintype "passive"))
      (node (ref "DS2") (pin "T1") (pinfunction "VSS_T1") (pintype "passive"))
      (node (ref "DS2") (pin "T9") (pinfunction "VSS_T9") (pintype "passive"))
      (node (ref "DS3") (pin "A9") (pinfunction "VSS_A9") (pintype "passive"))
      (node (ref "DS3") (pin "B1") (pinfunction "VSSQ_B1") (pintype "passive"))
      (node (ref "DS3") (pin "B3") (pinfunction "VSS_B3") (pintype "passive"))
      (node (ref "DS3") (pin "B9") (pinfunction "VSSQ_B9") (pintype "passive"))
      (node (ref "DS3") (pin "D1") (pinfunction "VSSQ_D1") (pintype "passive"))
      (node (ref "DS3") (pin "D8") (pinfunction "VSSQ_D8") (pintype "passive"))
      (node (ref "DS3") (pin "E1") (pinfunction "VSS_E1") (pintype "passive"))
      (node (ref "DS3") (pin "E2") (pinfunction "VSSQ_E2") (pintype "passive"))
      (node (ref "DS3") (pin "E8") (pinfunction "VSSQ_E8") (pintype "passive"))
      (node (ref "DS3") (pin "F9") (pinfunction "VSSQ_F9") (pintype "passive"))
      (node (ref "DS3") (pin "G1") (pinfunction "VSSQ_G1") (pintype "passive"))
      (node (ref "DS3") (pin "G8") (pinfunction "VSS_G8") (pintype "passive"))
      (node (ref "DS3") (pin "G9") (pinfunction "VSSQ_G9") (pintype "passive"))
      (node (ref "DS3") (pin "J2") (pinfunction "VSS_J2") (pintype "passive"))
      (node (ref "DS3") (pin "J8") (pinfunction "VSS_J8") (pintype "passive"))
      (node (ref "DS3") (pin "M1") (pinfunction "VSS_M1") (pintype "passive"))
      (node (ref "DS3") (pin "M9") (pinfunction "VSS_M9") (pintype "passive"))
      (node (ref "DS3") (pin "P1") (pinfunction "VSS_P1") (pintype "passive"))
      (node (ref "DS3") (pin "P9") (pinfunction "VSS_P9") (pintype "passive"))
      (node (ref "DS3") (pin "T1") (pinfunction "VSS_T1") (pintype "passive"))
      (node (ref "DS3") (pin "T9") (pinfunction "VSS_T9") (pintype "passive"))
      (node (ref "DS4") (pin "A9") (pinfunction "VSS_A9") (pintype "passive"))
      (node (ref "DS4") (pin "B1") (pinfunction "VSSQ_B1") (pintype "passive"))
      (node (ref "DS4") (pin "B3") (pinfunction "VSS_B3") (pintype "passive"))
      (node (ref "DS4") (pin "B9") (pinfunction "VSSQ_B9") (pintype "passive"))
      (node (ref "DS4") (pin "D1") (pinfunction "VSSQ_D1") (pintype "passive"))
      (node (ref "DS4") (pin "D8") (pinfunction "VSSQ_D8") (pintype "passive"))
      (node (ref "DS4") (pin "E1") (pinfunction "VSS_E1") (pintype "passive"))
      (node (ref "DS4") (pin "E2") (pinfunction "VSSQ_E2") (pintype "passive"))
      (node (ref "DS4") (pin "E8") (pinfunction "VSSQ_E8") (pintype "passive"))
      (node (ref "DS4") (pin "F9") (pinfunction "VSSQ_F9") (pintype "passive"))
      (node (ref "DS4") (pin "G1") (pinfunction "VSSQ_G1") (pintype "passive"))
      (node (ref "DS4") (pin "G8") (pinfunction "VSS_G8") (pintype "passive"))
      (node (ref "DS4") (pin "G9") (pinfunction "VSSQ_G9") (pintype "passive"))
      (node (ref "DS4") (pin "J2") (pinfunction "VSS_J2") (pintype "passive"))
      (node (ref "DS4") (pin "J8") (pinfunction "VSS_J8") (pintype "passive"))
      (node (ref "DS4") (pin "M1") (pinfunction "VSS_M1") (pintype "passive"))
      (node (ref "DS4") (pin "M9") (pinfunction "VSS_M9") (pintype "passive"))
      (node (ref "DS4") (pin "P1") (pinfunction "VSS_P1") (pintype "passive"))
      (node (ref "DS4") (pin "P9") (pinfunction "VSS_P9") (pintype "passive"))
      (node (ref "DS4") (pin "T1") (pinfunction "VSS_T1") (pintype "passive"))
      (node (ref "DS4") (pin "T9") (pinfunction "VSS_T9") (pintype "passive"))
    )
    (net (code "122") (name "VREF_A") (class "Default")
      (node (ref "DS1") (pin "H1") (pinfunction "VREFDQ_H1") (pintype "passive"))
      (node (ref "DS1") (pin "M8") (pinfunction "VREFCA_M8") (pintype "passive"))
      (node (ref "DS2") (pin "H1") (pinfunction "VREFDQ_H1") (pintype "passive"))
      (node (ref "DS2") (pin "M8") (pinfunction "VREFCA_M8") (pintype "passive"))
      (node (ref "DS3") (pin "H1") (pinfunction "VREFDQ_H1") (pintype "passive"))
      (node (ref "DS3") (pin "M8") (pinfunction "VREFCA_M8") (pintype "passive"))
      (node (ref "DS4") (pin "H1") (pinfunction "VREFDQ_H1") (pintype "passive"))
      (node (ref "DS4") (pin "M8") (pinfunction "VREFCA_M8") (pintype "passive"))
    )
    (net (code "123") (name "unconnected-(DS1-NC-PadJ1)") (class "Default")
      (node (ref "DS1") (pin "J1") (pinfunction "NC_J1") (pintype "passive"))
    )
    (net (code "124") (name "unconnected-(DS1-NC-PadJ9)") (class "Default")
      (node (ref "DS1") (pin "J9") (pinfunction "NC_J9") (pintype "passive"))
    )
    (net (code "125") (name "unconnected-(DS1-NC-PadL1)") (class "Default")
      (node (ref "DS1") (pin "L1") (pinfunction "NC_L1") (pintype "passive"))
    )
    (net (code "126") (name "unconnected-(DS1-NC-PadL9)") (class "Default")
      (node (ref "DS1") (pin "L9") (pinfunction "NC_L9") (pintype "passive"))
    )
    (net (code "127") (name "unconnected-(DS1-NC-PadM7)") (class "Default")
      (node (ref "DS1") (pin "M7") (pinfunction "NC_M7") (pintype "passive"))
    )
    (net (code "128") (name "unconnected-(DS2-NC-PadJ1)") (class "Default")
      (node (ref "DS2") (pin "J1") (pinfunction "NC_J1") (pintype "passive"))
    )
    (net (code "129") (name "unconnected-(DS2-NC-PadJ9)") (class "Default")
      (node (ref "DS2") (pin "J9") (pinfunction "NC_J9") (pintype "passive"))
    )
    (net (code "130") (name "unconnected-(DS2-NC-PadL1)") (class "Default")
      (node (ref "DS2") (pin "L1") (pinfunction "NC_L1") (pintype "passive"))
    )
    (net (code "131") (name "unconnected-(DS2-NC-PadL9)") (class "Default")
      (node (ref "DS2") (pin "L9") (pinfunction "NC_L9") (pintype "passive"))
    )
    (net (code "132") (name "unconnected-(DS2-NC-PadM7)") (class "Default")
      (node (ref "DS2") (pin "M7") (pinfunction "NC_M7") (pintype "passive"))
    )
    (net (code "133") (name "unconnected-(DS3-NC-PadJ1)") (class "Default")
      (node (ref "DS3") (pin "J1") (pinfunction "NC_J1") (pintype "passive"))
    )
    (net (code "134") (name "unconnected-(DS3-NC-PadJ9)") (class "Default")
      (node (ref "DS3") (pin "J9") (pinfunction "NC_J9") (pintype "passive"))
    )
    (net (code "135") (name "unconnected-(DS3-NC-PadL1)") (class "Default")
      (node (ref "DS3") (pin "L1") (pinfunction "NC_L1") (pintype "passive"))
    )
    (net (code "136") (name "unconnected-(DS3-NC-PadL9)") (class "Default")
      (node (ref "DS3") (pin "L9") (pinfunction "NC_L9") (pintype "passive"))
    )
    (net (code "137") (name "unconnected-(DS3-NC-PadM7)") (class "Default")
      (node (ref "DS3") (pin "M7") (pinfunction "NC_M7") (pintype "passive"))
    )
    (net (code "138") (name "unconnected-(DS4-NC-PadJ1)") (class "Default")
      (node (ref "DS4") (pin "J1") (pinfunction "NC_J1") (pintype "passive"))
    )
    (net (code "139") (name "unconnected-(DS4-NC-PadJ9)") (class "Default")
      (node (ref "DS4") (pin "J9") (pinfunction "NC_J9") (pintype "passive"))
    )
    (net (code "140") (name "unconnected-(DS4-NC-PadL1)") (class "Default")
      (node (ref "DS4") (pin "L1") (pinfunction "NC_L1") (pintype "passive"))
    )
    (net (code "141") (name "unconnected-(DS4-NC-PadL9)") (class "Default")
      (node (ref "DS4") (pin "L9") (pinfunction "NC_L9") (pintype "passive"))
    )
    (net (code "142") (name "unconnected-(DS4-NC-PadM7)") (class "Default")
      (node (ref "DS4") (pin "M7") (pinfunction "NC_M7") (pintype "passive"))
    )
  )
)
